# schematic.net
KiCad netlist of a schematic drawn in Altium Designer
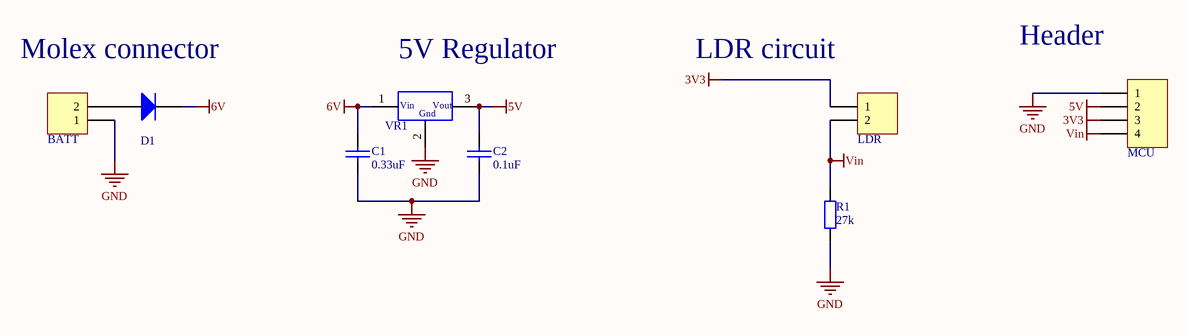
[diagram p0: schematic.SchDoc]

(export (version "E")
  (design (tool "Eeschema 10.0.6"))
  (components
    (comp (ref "BATT")
      (value "2 Way")
      (footprint "ECE-600102STTH")
      (description "HEADER POLARISED 2WAY TH")
      (libsource (lib "EceParts") (part "Header 2"))
    )
    (comp (ref "C1")
      (value "0.33uF")
      (footprint "CCAP-5P0")
      (description "TH ceramic capacitor with 5mm pitch")
      (libsource (lib "EE209_Library") (part "CerCap_TH_5P0"))
    )
    (comp (ref "C2")
      (value "0.1uF")
      (footprint "CCAP-5P0")
      (description "TH ceramic capacitor with 5mm pitch")
      (libsource (lib "EE209_Library") (part "CerCap_TH_5P0"))
    )
    (comp (ref "D1")
      (value "1N4007")
      (footprint "1N4007-MFG")
      (description "1N4007 1000V standard axial diode")
      (libsource (lib "EE209_Library") (part "1N4007_TH_4AX0"))
    )
    (comp (ref "LDR")
      (value "2 Way")
      (footprint "ECE-600102STTH")
      (description "HEADER POLARISED 2WAY TH")
      (libsource (lib "") (part "Header 2_1"))
    )
    (comp (ref "MCU")
      (value "4 Way")
      (footprint "ECE-600104STTH")
      (description "HEADER POLARISED 4WAY TH")
      (libsource (lib "EceParts") (part "Header 4"))
    )
    (comp (ref "R1")
      (value "27k")
      (footprint "AXIAL-0.4")
      (description "Through hole resistor")
      (fields (field (name "PUBLISHER") "Altium Limited"))
      (libsource (lib "EE209_Library") (part "Res_TH_0AX4"))
    )
    (comp (ref "VR1")
      (value "L7805CV")
      (footprint "ECE-TO220ABTH")
      (description "REG POSITIVE 5V TO220")
      (libsource (lib "EceParts") (part "VoltRegBig"))
    )
  )
  (nets
    (net (code "1") (name "3V3") (class "Default")
      (node (ref "LDR") (pin "1") (pinfunction "1_1") (pintype "passive"))
      (node (ref "MCU") (pin "3") (pinfunction "3_3") (pintype "passive"))
    )
    (net (code "2") (name "5V") (class "Default")
      (node (ref "C2") (pin "1") (pinfunction "1_1") (pintype "passive"))
      (node (ref "MCU") (pin "2") (pinfunction "2_2") (pintype "passive"))
      (node (ref "VR1") (pin "3") (pinfunction "Vout_3") (pintype "passive"))
    )
    (net (code "3") (name "6V") (class "Default")
      (node (ref "C1") (pin "1") (pinfunction "1_1") (pintype "passive"))
      (node (ref "D1") (pin "2") (pinfunction "K_2") (pintype "passive"))
      (node (ref "VR1") (pin "1") (pinfunction "Vin_1") (pintype "passive"))
    )
    (net (code "4") (name "GND") (class "Default")
      (node (ref "BATT") (pin "1") (pinfunction "1_1") (pintype "passive"))
      (node (ref "C1") (pin "2") (pinfunction "2_2") (pintype "passive"))
      (node (ref "C2") (pin "2") (pinfunction "2_2") (pintype "passive"))
      (node (ref "MCU") (pin "1") (pinfunction "1_1") (pintype "passive"))
      (node (ref "R1") (pin "1") (pinfunction "1_1") (pintype "passive"))
      (node (ref "VR1") (pin "2") (pinfunction "Gnd_2") (pintype "passive"))
    )
    (net (code "5") (name "Net-(D1-A)") (class "Default")
      (node (ref "BATT") (pin "2") (pinfunction "2_2") (pintype "passive"))
      (node (ref "D1") (pin "1") (pinfunction "A_1") (pintype "passive"))
    )
    (net (code "6") (name "Vin") (class "Default")
      (node (ref "LDR") (pin "2") (pinfunction "2_2") (pintype "passive"))
      (node (ref "MCU") (pin "4") (pinfunction "4_4") (pintype "passive"))
      (node (ref "R1") (pin "2") (pinfunction "2_2") (pintype "passive"))
    )
  )
)
